# main.net
KiCad netlist of a schematic drawn in Altium Designer
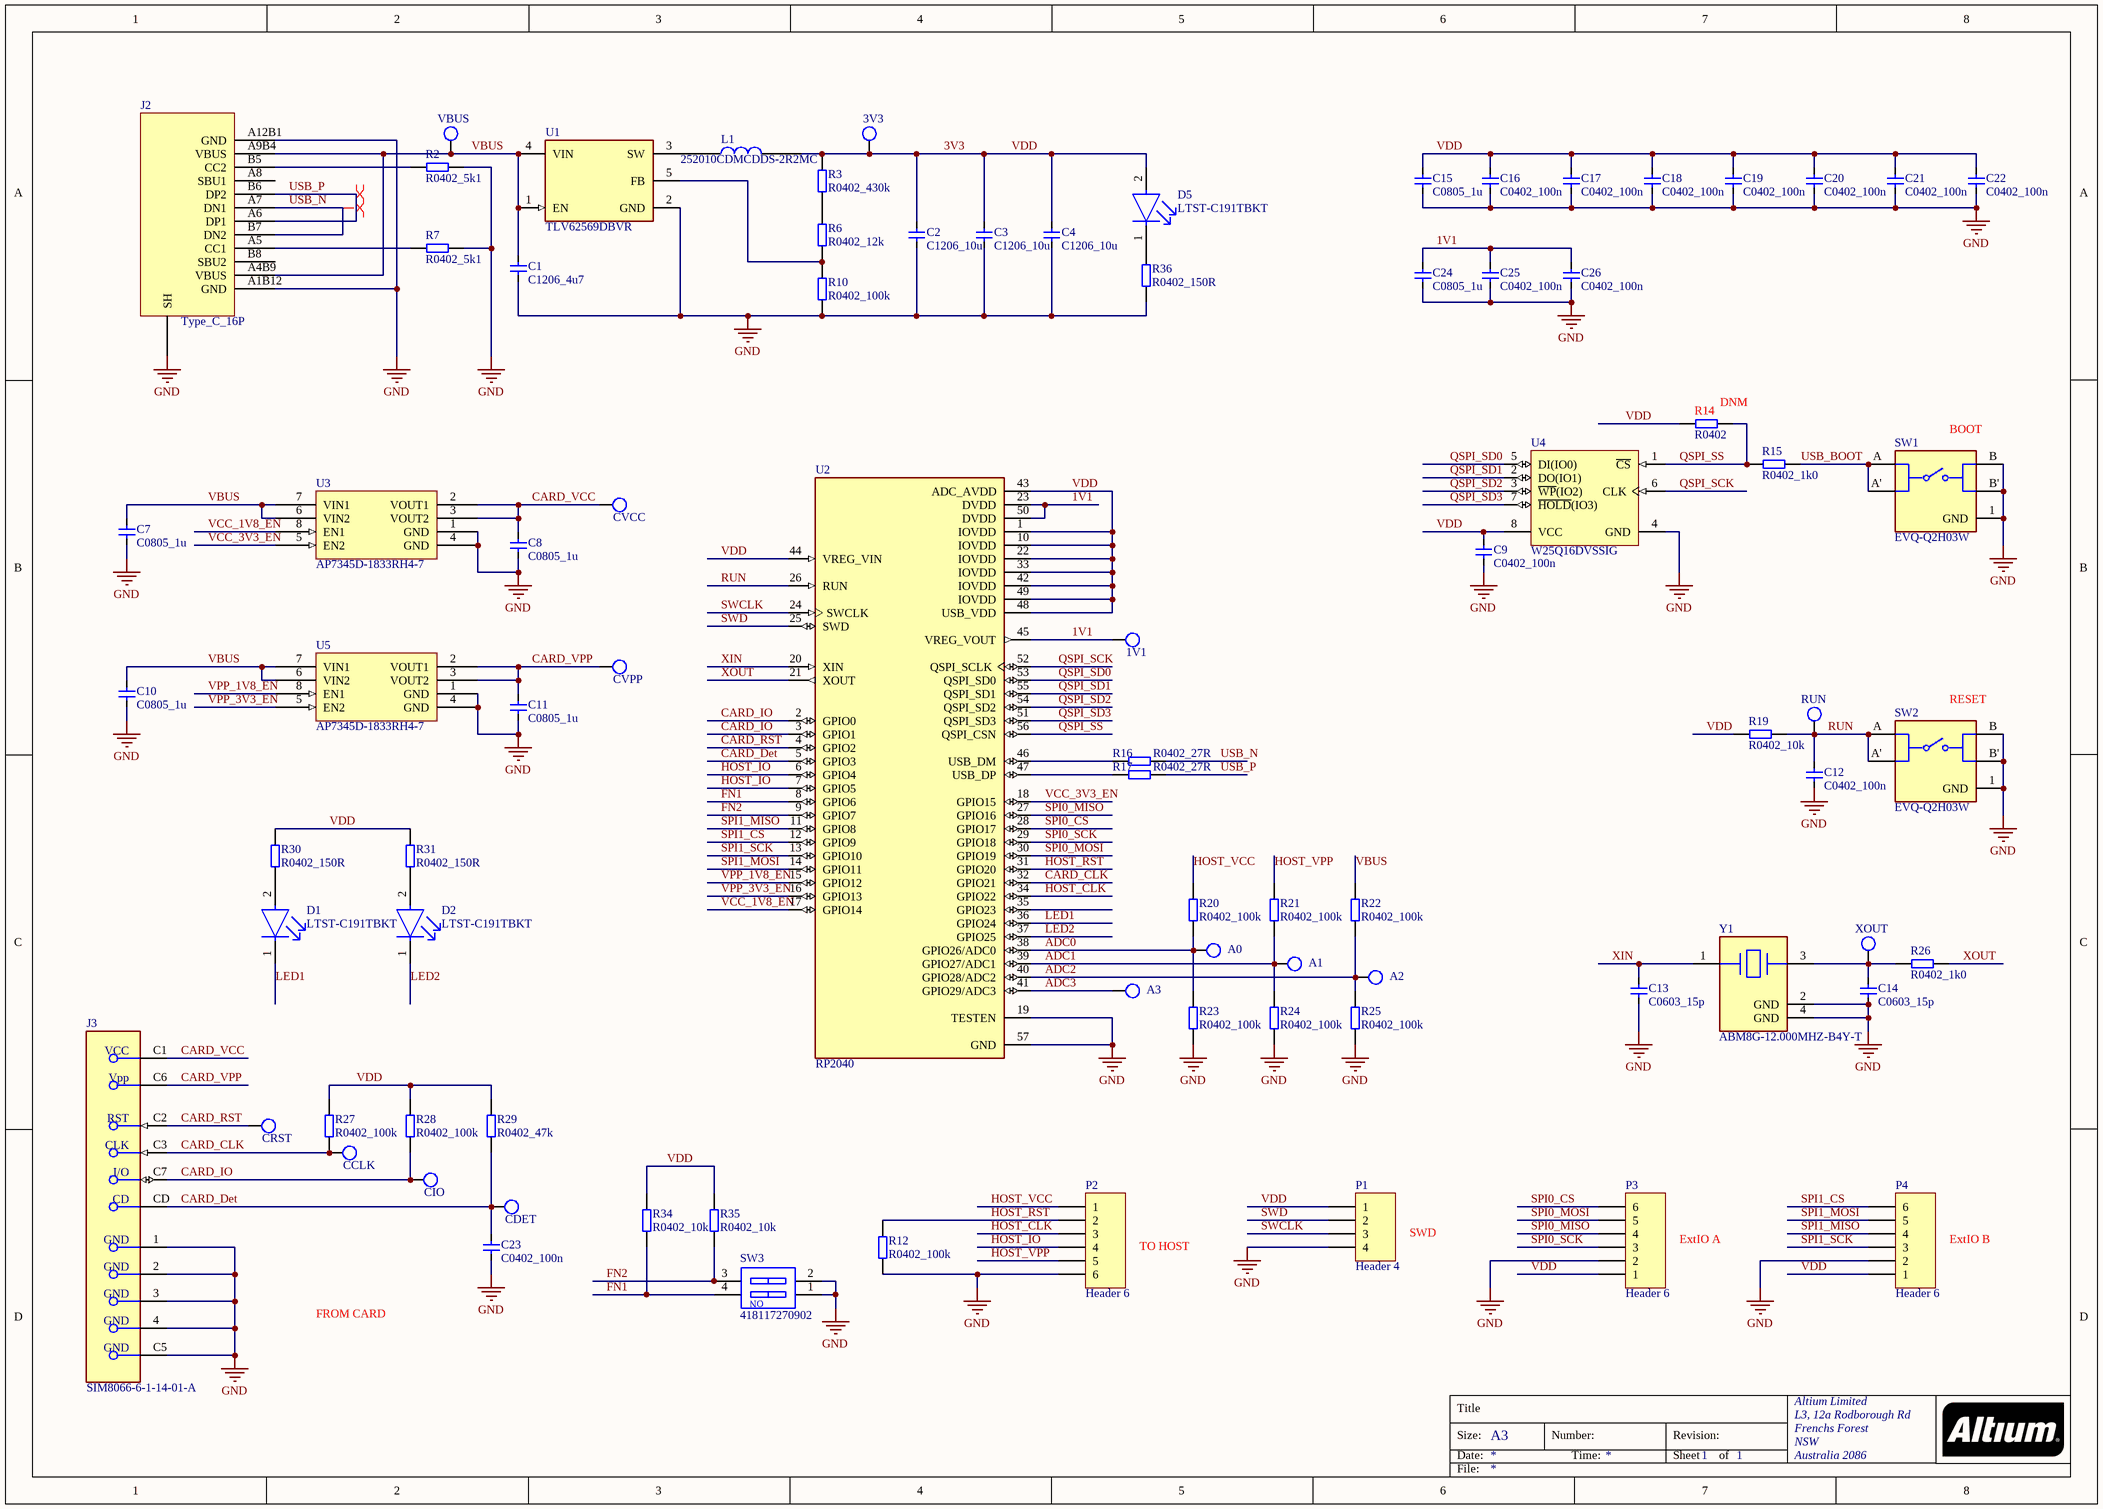
[diagram p0: main.SchDoc]

(export (version "E")
  (design (tool "Eeschema 10.0.6"))
  (components
    (comp (ref "1V1")
      (value "TestPin 1.2R 0.3R")
      (footprint "TestPin_1.2R_0.3R")
      (libsource (lib "LuLib") (part "TestPin 1.2R 0.3R"))
    )
    (comp (ref "3V3")
      (value "TestPin 1.2R 0.3R")
      (footprint "TestPin_1.2R_0.3R")
      (libsource (lib "LuLib") (part "TestPin 1.2R 0.3R"))
    )
    (comp (ref "A0")
      (value "TestPin 1.2R 0.3R")
      (footprint "TestPin_1.2R_0.3R")
      (libsource (lib "LuLib") (part "TestPin 1.2R 0.3R"))
    )
    (comp (ref "A1")
      (value "TestPin 1.2R 0.3R")
      (footprint "TestPin_1.2R_0.3R")
      (libsource (lib "LuLib") (part "TestPin 1.2R 0.3R"))
    )
    (comp (ref "A2")
      (value "TestPin 1.2R 0.3R")
      (footprint "TestPin_1.2R_0.3R")
      (libsource (lib "LuLib") (part "TestPin 1.2R 0.3R"))
    )
    (comp (ref "A3")
      (value "TestPin 1.2R 0.3R")
      (footprint "TestPin_1.2R_0.3R")
      (libsource (lib "LuLib") (part "TestPin 1.2R 0.3R"))
    )
    (comp (ref "C1")
      (value "C1206_4u7")
      (footprint "C1206")
      (fields (field (name "TOLERANCE") "0.1%"))
      (libsource (lib "NyaMoe Internal Altium Server") (part "Cap"))
    )
    (comp (ref "C2")
      (value "C1206_10u")
      (footprint "C1206")
      (fields (field (name "TOLERANCE") "0.1%"))
      (libsource (lib "NyaMoe Internal Altium Server") (part "Cap"))
    )
    (comp (ref "C3")
      (value "C1206_10u")
      (footprint "C1206")
      (fields (field (name "TOLERANCE") "0.1%"))
      (libsource (lib "NyaMoe Internal Altium Server") (part "Cap"))
    )
    (comp (ref "C4")
      (value "C1206_10u")
      (footprint "C1206")
      (fields (field (name "TOLERANCE") "0.1%"))
      (libsource (lib "NyaMoe Internal Altium Server") (part "Cap"))
    )
    (comp (ref "C7")
      (value "C0805_1u")
      (footprint "C0805")
      (fields (field (name "TOLERANCE") "0.1%"))
      (libsource (lib "NyaMoe Internal Altium Server") (part "Cap"))
    )
    (comp (ref "C8")
      (value "C0805_1u")
      (footprint "C0805")
      (fields (field (name "TOLERANCE") "0.1%"))
      (libsource (lib "NyaMoe Internal Altium Server") (part "Cap"))
    )
    (comp (ref "C9")
      (value "C0402_100n")
      (footprint "C0402")
      (fields (field (name "TOLERANCE") "0.1%"))
      (libsource (lib "NyaMoe Internal Altium Server") (part "Cap"))
    )
    (comp (ref "C10")
      (value "C0805_1u")
      (footprint "C0805")
      (fields (field (name "TOLERANCE") "0.1%"))
      (libsource (lib "NyaMoe Internal Altium Server") (part "Cap"))
    )
    (comp (ref "C11")
      (value "C0805_1u")
      (footprint "C0805")
      (fields (field (name "TOLERANCE") "0.1%"))
      (libsource (lib "NyaMoe Internal Altium Server") (part "Cap"))
    )
    (comp (ref "C12")
      (value "C0402_100n")
      (footprint "C0402")
      (fields (field (name "TOLERANCE") "0.1%"))
      (libsource (lib "NyaMoe Internal Altium Server") (part "Cap"))
    )
    (comp (ref "C13")
      (value "C0603_15p")
      (footprint "C0603")
      (fields (field (name "TOLERANCE") "0.05%"))
      (libsource (lib "NyaMoe Internal Altium Server") (part "Cap"))
    )
    (comp (ref "C14")
      (value "C0603_15p")
      (footprint "C0603")
      (fields (field (name "TOLERANCE") "0.05%"))
      (libsource (lib "NyaMoe Internal Altium Server") (part "Cap"))
    )
    (comp (ref "C15")
      (value "C0805_1u")
      (footprint "C0805")
      (fields (field (name "TOLERANCE") "0.1%"))
      (libsource (lib "NyaMoe Internal Altium Server") (part "Cap"))
    )
    (comp (ref "C16")
      (value "C0402_100n")
      (footprint "C0402")
      (fields (field (name "TOLERANCE") "0.1%"))
      (libsource (lib "NyaMoe Internal Altium Server") (part "Cap"))
    )
    (comp (ref "C17")
      (value "C0402_100n")
      (footprint "C0402")
      (fields (field (name "TOLERANCE") "0.1%"))
      (libsource (lib "NyaMoe Internal Altium Server") (part "Cap"))
    )
    (comp (ref "C18")
      (value "C0402_100n")
      (footprint "C0402")
      (fields (field (name "TOLERANCE") "0.1%"))
      (libsource (lib "NyaMoe Internal Altium Server") (part "Cap"))
    )
    (comp (ref "C19")
      (value "C0402_100n")
      (footprint "C0402")
      (fields (field (name "TOLERANCE") "0.1%"))
      (libsource (lib "NyaMoe Internal Altium Server") (part "Cap"))
    )
    (comp (ref "C20")
      (value "C0402_100n")
      (footprint "C0402")
      (fields (field (name "TOLERANCE") "0.1%"))
      (libsource (lib "NyaMoe Internal Altium Server") (part "Cap"))
    )
    (comp (ref "C21")
      (value "C0402_100n")
      (footprint "C0402")
      (fields (field (name "TOLERANCE") "0.1%"))
      (libsource (lib "NyaMoe Internal Altium Server") (part "Cap"))
    )
    (comp (ref "C22")
      (value "C0402_100n")
      (footprint "C0402")
      (fields (field (name "TOLERANCE") "0.1%"))
      (libsource (lib "NyaMoe Internal Altium Server") (part "Cap"))
    )
    (comp (ref "C23")
      (value "C0402_100n")
      (footprint "C0402")
      (fields (field (name "TOLERANCE") "0.1%"))
      (libsource (lib "NyaMoe Internal Altium Server") (part "Cap"))
    )
    (comp (ref "C24")
      (value "C0805_1u")
      (footprint "C0805")
      (fields (field (name "TOLERANCE") "0.1%"))
      (libsource (lib "NyaMoe Internal Altium Server") (part "Cap"))
    )
    (comp (ref "C25")
      (value "C0402_100n")
      (footprint "C0402")
      (fields (field (name "TOLERANCE") "0.1%"))
      (libsource (lib "NyaMoe Internal Altium Server") (part "Cap"))
    )
    (comp (ref "C26")
      (value "C0402_100n")
      (footprint "C0402")
      (fields (field (name "TOLERANCE") "0.1%"))
      (libsource (lib "NyaMoe Internal Altium Server") (part "Cap"))
    )
    (comp (ref "CCLK")
      (value "TestPin 1.2R 0.3R")
      (footprint "TestPin_1.2R_0.3R")
      (libsource (lib "LuLib") (part "TestPin 1.2R 0.3R"))
    )
    (comp (ref "CDET")
      (value "TestPin 1.2R 0.3R")
      (footprint "TestPin_1.2R_0.3R")
      (libsource (lib "LuLib") (part "TestPin 1.2R 0.3R"))
    )
    (comp (ref "CIO")
      (value "TestPin 1.2R 0.3R")
      (footprint "TestPin_1.2R_0.3R")
      (libsource (lib "LuLib") (part "TestPin 1.2R 0.3R"))
    )
    (comp (ref "CRST")
      (value "TestPin 1.2R 0.3R")
      (footprint "TestPin_1.2R_0.3R")
      (libsource (lib "LuLib") (part "TestPin 1.2R 0.3R"))
    )
    (comp (ref "CVCC")
      (value "TestPin 1.2R 0.3R")
      (footprint "TestPin_1.2R_0.3R")
      (libsource (lib "LuLib") (part "TestPin 1.2R 0.3R"))
    )
    (comp (ref "CVPP")
      (value "TestPin 1.2R 0.3R")
      (footprint "TestPin_1.2R_0.3R")
      (libsource (lib "LuLib") (part "TestPin 1.2R 0.3R"))
    )
    (comp (ref "D1")
      (value "LTST-C191TBKT")
      (footprint "FP-LTST-C191TBKT-MFG")
      (description "LED BLUE CLEAR CHIP SMD")
      (libsource (lib "Altium Content Vault") (part "8706943c75ba83719d021d2fdc84c58"))
    )
    (comp (ref "D2")
      (value "LTST-C191TBKT")
      (footprint "FP-LTST-C191TBKT-MFG")
      (description "LED BLUE CLEAR CHIP SMD")
      (libsource (lib "Altium Content Vault") (part "8706943c75ba83719d021d2fdc84c58"))
    )
    (comp (ref "D5")
      (value "LTST-C191TBKT")
      (footprint "FP-LTST-C191TBKT-MFG")
      (description "LED BLUE CLEAR CHIP SMD")
      (libsource (lib "Altium Content Vault") (part "8706943c75ba83719d021d2fdc84c58"))
    )
    (comp (ref "J2")
      (value "Type_C_16P")
      (footprint "Type_C_16P")
      (libsource (lib "LuLib") (part "Type_C_16P"))
    )
    (comp (ref "J3")
      (value "SIM8066-6-1-14-01-A")
      (footprint "FP-SIM8066-6-1-14-01-A-MFG")
      (description "SIM8066-6-1-14-01-A Memory Card Connectors 1.44mm Nano SIM Conn w/Peg and Switch")
      (libsource (lib "Altium Content Vault") (part "1421b091a134f49a34fd3b08e40bfdd"))
    )
    (comp (ref "L1")
      (value "252010CDMCDDS-2R2MC")
      (footprint "INDC2520X10N")
      (description "Fixed Ind 2.2UH 2.5A 97 Mohm SMD")
      (libsource (lib "NyaMoe Internal Altium Server") (part "252010CDMCDDS-2R2MC"))
    )
    (comp (ref "P1")
      (value "Header 4")
      (footprint "HDR1X4")
      (description "Header, 4-Pin")
      (fields (field (name "PUBLISHER") "Altium Limited"))
      (libsource (lib "Miscellaneous Connectors") (part "Header 4"))
    )
    (comp (ref "P2")
      (value "Header 6")
      (footprint "HDR1X6")
      (description "Header, 6-Pin")
      (fields (field (name "PUBLISHER") "Altium Limited"))
      (libsource (lib "Miscellaneous Connectors") (part "Header 6"))
    )
    (comp (ref "P3")
      (value "Header 6")
      (footprint "HDR1X6")
      (description "Header, 6-Pin")
      (fields (field (name "PUBLISHER") "Altium Limited"))
      (libsource (lib "") (part "Header 6_1"))
    )
    (comp (ref "P4")
      (value "Header 6")
      (footprint "HDR1X6")
      (description "Header, 6-Pin")
      (fields (field (name "PUBLISHER") "Altium Limited"))
      (libsource (lib "") (part "Header 6_1"))
    )
    (comp (ref "R2")
      (value "R0402_5k1")
      (footprint "R0402")
      (fields (field (name "TOLERANCE") "1%"))
      (libsource (lib "NyaMoe Internal Altium Server") (part "Res"))
    )
    (comp (ref "R3")
      (value "R0402_430k")
      (footprint "R0402")
      (fields (field (name "TOLERANCE") "1%"))
      (libsource (lib "NyaMoe Internal Altium Server") (part "Res"))
    )
    (comp (ref "R6")
      (value "R0402_12k")
      (footprint "R0402")
      (fields (field (name "TOLERANCE") "1%"))
      (libsource (lib "NyaMoe Internal Altium Server") (part "Res"))
    )
    (comp (ref "R7")
      (value "R0402_5k1")
      (footprint "R0402")
      (fields (field (name "TOLERANCE") "1%"))
      (libsource (lib "NyaMoe Internal Altium Server") (part "Res"))
    )
    (comp (ref "R10")
      (value "R0402_100k")
      (footprint "R0402")
      (fields (field (name "TOLERANCE") "1%"))
      (libsource (lib "NyaMoe Internal Altium Server") (part "Res"))
    )
    (comp (ref "R12")
      (value "R0402_100k")
      (footprint "R0402")
      (fields (field (name "TOLERANCE") "1%"))
      (libsource (lib "NyaMoe Internal Altium Server") (part "Res"))
    )
    (comp (ref "R14")
      (value "R0402")
      (footprint "R0402")
      (fields (field (name "TOLERANCE") "1%"))
      (libsource (lib "NyaMoe Internal Altium Server") (part "Res"))
    )
    (comp (ref "R15")
      (value "R0402_1k0")
      (footprint "R0402")
      (fields (field (name "TOLERANCE") "1%"))
      (libsource (lib "NyaMoe Internal Altium Server") (part "Res"))
    )
    (comp (ref "R16")
      (value "R0402_27R")
      (footprint "R0402")
      (fields (field (name "TOLERANCE") "1%"))
      (libsource (lib "NyaMoe Internal Altium Server") (part "Res"))
    )
    (comp (ref "R17")
      (value "R0402_27R")
      (footprint "R0402")
      (fields (field (name "TOLERANCE") "1%"))
      (libsource (lib "NyaMoe Internal Altium Server") (part "Res"))
    )
    (comp (ref "R19")
      (value "R0402_10k")
      (footprint "R0402")
      (fields (field (name "TOLERANCE") "1%"))
      (libsource (lib "NyaMoe Internal Altium Server") (part "Res"))
    )
    (comp (ref "R20")
      (value "R0402_100k")
      (footprint "R0402")
      (fields (field (name "TOLERANCE") "1%"))
      (libsource (lib "NyaMoe Internal Altium Server") (part "Res"))
    )
    (comp (ref "R21")
      (value "R0402_100k")
      (footprint "R0402")
      (fields (field (name "TOLERANCE") "1%"))
      (libsource (lib "NyaMoe Internal Altium Server") (part "Res"))
    )
    (comp (ref "R22")
      (value "R0402_100k")
      (footprint "R0402")
      (fields (field (name "TOLERANCE") "1%"))
      (libsource (lib "NyaMoe Internal Altium Server") (part "Res"))
    )
    (comp (ref "R23")
      (value "R0402_100k")
      (footprint "R0402")
      (fields (field (name "TOLERANCE") "1%"))
      (libsource (lib "NyaMoe Internal Altium Server") (part "Res"))
    )
    (comp (ref "R24")
      (value "R0402_100k")
      (footprint "R0402")
      (fields (field (name "TOLERANCE") "1%"))
      (libsource (lib "NyaMoe Internal Altium Server") (part "Res"))
    )
    (comp (ref "R25")
      (value "R0402_100k")
      (footprint "R0402")
      (fields (field (name "TOLERANCE") "1%"))
      (libsource (lib "NyaMoe Internal Altium Server") (part "Res"))
    )
    (comp (ref "R26")
      (value "R0402_1k0")
      (footprint "R0402")
      (fields (field (name "TOLERANCE") "1%"))
      (libsource (lib "NyaMoe Internal Altium Server") (part "Res"))
    )
    (comp (ref "R27")
      (value "R0402_100k")
      (footprint "R0402")
      (fields (field (name "TOLERANCE") "1%"))
      (libsource (lib "NyaMoe Internal Altium Server") (part "Res"))
    )
    (comp (ref "R28")
      (value "R0402_100k")
      (footprint "R0402")
      (fields (field (name "TOLERANCE") "1%"))
      (libsource (lib "NyaMoe Internal Altium Server") (part "Res"))
    )
    (comp (ref "R29")
      (value "R0402_47k")
      (footprint "R0402")
      (fields (field (name "TOLERANCE") "1%"))
      (libsource (lib "NyaMoe Internal Altium Server") (part "Res"))
    )
    (comp (ref "R30")
      (value "R0402_150R")
      (footprint "R0402")
      (fields (field (name "TOLERANCE") "1%"))
      (libsource (lib "NyaMoe Internal Altium Server") (part "Res"))
    )
    (comp (ref "R31")
      (value "R0402_150R")
      (footprint "R0402")
      (fields (field (name "TOLERANCE") "1%"))
      (libsource (lib "NyaMoe Internal Altium Server") (part "Res"))
    )
    (comp (ref "R34")
      (value "R0402_10k")
      (footprint "R0402")
      (fields (field (name "TOLERANCE") "1%"))
      (libsource (lib "NyaMoe Internal Altium Server") (part "Res"))
    )
    (comp (ref "R35")
      (value "R0402_10k")
      (footprint "R0402")
      (fields (field (name "TOLERANCE") "1%"))
      (libsource (lib "NyaMoe Internal Altium Server") (part "Res"))
    )
    (comp (ref "R36")
      (value "R0402_150R")
      (footprint "R0402")
      (fields (field (name "TOLERANCE") "1%"))
      (libsource (lib "NyaMoe Internal Altium Server") (part "Res"))
    )
    (comp (ref "RUN")
      (value "TestPin 1.2R 0.3R")
      (footprint "TestPin_1.2R_0.3R")
      (libsource (lib "LuLib") (part "TestPin 1.2R 0.3R"))
    )
    (comp (ref "SW1")
      (value "EVQ-Q2H03W")
      (footprint "FP-EVQ-Q2H03W-MFG")
      (description "SWITCH TACTILE SPST-NO 0.02A 15V")
      (fields
        (field (name "OCTOPART") "https://octopart.com/evq-q2h03w-panasonic-1368538")
        (field (name "MANUFACTURER") "Panasonic Electronic Components")
      )
      (libsource (lib "Altium Content Vault") (part "771f9546cad75bebae6a9b98152ef8d"))
    )
    (comp (ref "SW2")
      (value "EVQ-Q2H03W")
      (footprint "FP-EVQ-Q2H03W-MFG")
      (description "SWITCH TACTILE SPST-NO 0.02A 15V")
      (fields
        (field (name "OCTOPART") "https://octopart.com/evq-q2h03w-panasonic-1368538")
        (field (name "MANUFACTURER") "Panasonic Electronic Components")
      )
      (libsource (lib "Altium Content Vault") (part "771f9546cad75bebae6a9b98152ef8d"))
    )
    (comp (ref "SW3")
      (value "418117270902")
      (footprint "418117270902")
      (libsource (lib "Altium Content Vault") (part "DIP-2"))
    )
    (comp (ref "U1")
      (value "TLV62569DBVR")
      (footprint "FP-DBV0005A-MFG")
      (description "IC REG BUCK ADJ 2A SOT23-5")
      (libsource (lib "Altium Content Vault") (part "f8671745ee5fb9a493b385c735b730b"))
    )
    (comp (ref "U2")
      (value "RP2040")
      (footprint "QFN40P700X700X90-57N")
      (description "RP2040 chip for Raspberry Pi Pico - ARM?Cortex?M0+ MCU 32-Bit")
      (fields (field (name "MF") "Raspberry Pi"))
      (libsource (lib "NyaMoe Internal Altium Server") (part "RP2040"))
    )
    (comp (ref "U3")
      (value "AP7345D-1833RH4-7")
      (footprint "SON127P600-8N")
      (description "Active Positive e4 Fixed Linear Voltage Regulator IC -40C~85C TA 300mA 300mA 5.25V")
      (libsource (lib "NyaMoe Internal Altium Server") (part "AP7345D"))
    )
    (comp (ref "U4")
      (value "W25Q16DVSSIG")
      (footprint "WINB-W25Q16DVSSIG-8_M")
      (description "IC FLASH 16MBIT 104MHZ 8SOIC")
      (fields (field (name "MANUFACTURER") "Winbond"))
      (libsource (lib "Altium Content Vault") (part "WINB-W25Q16DVSSIG-8"))
    )
    (comp (ref "U5")
      (value "AP7345D-1833RH4-7")
      (footprint "SON127P600-8N")
      (description "Active Positive e4 Fixed Linear Voltage Regulator IC -40C~85C TA 300mA 300mA 5.25V")
      (libsource (lib "NyaMoe Internal Altium Server") (part "AP7345D"))
    )
    (comp (ref "VBUS")
      (value "TestPin 1.2R 0.3R")
      (footprint "TestPin_1.2R_0.3R")
      (libsource (lib "LuLib") (part "TestPin 1.2R 0.3R"))
    )
    (comp (ref "XOUT")
      (value "TestPin 1.2R 0.3R")
      (footprint "TestPin_1.2R_0.3R")
      (libsource (lib "LuLib") (part "TestPin 1.2R 0.3R"))
    )
    (comp (ref "Y1")
      (value "ABM8G-12.000MHZ-B4Y-T")
      (footprint "FP-ABM8G-MFG")
      (description "Crystal 12MHz ±30ppm (Tol) ±30ppm (Stability) 10pF FUND 120Ω 4-Pin SMD T/R")
      (fields (field (name "TOLERANCE") "30ppm"))
      (libsource (lib "Altium Content Vault") (part "48e526d86b7f2615d98721063c72f49"))
    )
  )
  (nets
    (net (code "1") (name "/1V1") (class "Default")
      (node (ref "1V1") (pin "0") (pinfunction "0_0") (pintype "passive"))
      (node (ref "C24") (pin "1") (pinfunction "1_1") (pintype "passive"))
      (node (ref "C25") (pin "1") (pinfunction "1_1") (pintype "passive"))
      (node (ref "C26") (pin "1") (pinfunction "1_1") (pintype "passive"))
      (node (ref "U2") (pin "23") (pinfunction "DVDD_23") (pintype "power_in"))
      (node (ref "U2") (pin "45") (pinfunction "VREG_VOUT_45") (pintype "output"))
      (node (ref "U2") (pin "50") (pinfunction "DVDD_50") (pintype "power_in"))
    )
    (net (code "2") (name "/3V3") (class "Default")
      (node (ref "3V3") (pin "0") (pinfunction "0_0") (pintype "passive"))
      (node (ref "C15") (pin "1") (pinfunction "1_1") (pintype "passive"))
      (node (ref "C16") (pin "1") (pinfunction "1_1") (pintype "passive"))
      (node (ref "C17") (pin "1") (pinfunction "1_1") (pintype "passive"))
      (node (ref "C18") (pin "1") (pinfunction "1_1") (pintype "passive"))
      (node (ref "C19") (pin "1") (pinfunction "1_1") (pintype "passive"))
      (node (ref "C2") (pin "1") (pinfunction "1_1") (pintype "passive"))
      (node (ref "C20") (pin "1") (pinfunction "1_1") (pintype "passive"))
      (node (ref "C21") (pin "1") (pinfunction "1_1") (pintype "passive"))
      (node (ref "C22") (pin "1") (pinfunction "1_1") (pintype "passive"))
      (node (ref "C3") (pin "1") (pinfunction "1_1") (pintype "passive"))
      (node (ref "C4") (pin "1") (pinfunction "1_1") (pintype "passive"))
      (node (ref "C9") (pin "1") (pinfunction "1_1") (pintype "passive"))
      (node (ref "D5") (pin "2") (pinfunction "A_2") (pintype "passive"))
      (node (ref "L1") (pin "2") (pinfunction "2_2") (pintype "passive"))
      (node (ref "P1") (pin "1") (pinfunction "1_1") (pintype "passive"))
      (node (ref "P3") (pin "1") (pinfunction "1_1") (pintype "passive"))
      (node (ref "P4") (pin "1") (pinfunction "1_1") (pintype "passive"))
      (node (ref "R14") (pin "1") (pinfunction "1_1") (pintype "passive"))
      (node (ref "R19") (pin "1") (pinfunction "1_1") (pintype "passive"))
      (node (ref "R27") (pin "2") (pinfunction "2_2") (pintype "passive"))
      (node (ref "R28") (pin "2") (pinfunction "2_2") (pintype "passive"))
      (node (ref "R29") (pin "2") (pinfunction "2_2") (pintype "passive"))
      (node (ref "R3") (pin "2") (pinfunction "2_2") (pintype "passive"))
      (node (ref "R30") (pin "2") (pinfunction "2_2") (pintype "passive"))
      (node (ref "R31") (pin "2") (pinfunction "2_2") (pintype "passive"))
      (node (ref "R34") (pin "2") (pinfunction "2_2") (pintype "passive"))
      (node (ref "R35") (pin "2") (pinfunction "2_2") (pintype "passive"))
      (node (ref "U2") (pin "1") (pinfunction "IOVDD_1") (pintype "power_in"))
      (node (ref "U2") (pin "10") (pinfunction "IOVDD_10") (pintype "power_in"))
      (node (ref "U2") (pin "22") (pinfunction "IOVDD_22") (pintype "power_in"))
      (node (ref "U2") (pin "33") (pinfunction "IOVDD_33") (pintype "power_in"))
      (node (ref "U2") (pin "42") (pinfunction "IOVDD_42") (pintype "power_in"))
      (node (ref "U2") (pin "43") (pinfunction "ADC_AVDD_43") (pintype "power_in"))
      (node (ref "U2") (pin "44") (pinfunction "VREG_VIN_44") (pintype "input"))
      (node (ref "U2") (pin "48") (pinfunction "USB_VDD_48") (pintype "power_in"))
      (node (ref "U2") (pin "49") (pinfunction "IOVDD_49") (pintype "power_in"))
      (node (ref "U4") (pin "8") (pinfunction "VCC_8") (pintype "power_in"))
    )
    (net (code "3") (name "/ADC0") (class "Default")
      (node (ref "A0") (pin "0") (pinfunction "0_0") (pintype "passive"))
      (node (ref "R20") (pin "1") (pinfunction "1_1") (pintype "passive"))
      (node (ref "R23") (pin "2") (pinfunction "2_2") (pintype "passive"))
      (node (ref "U2") (pin "38") (pinfunction "GPIO26/ADC0_38") (pintype "bidirectional"))
    )
    (net (code "4") (name "/ADC1") (class "Default")
      (node (ref "A1") (pin "0") (pinfunction "0_0") (pintype "passive"))
      (node (ref "R21") (pin "1") (pinfunction "1_1") (pintype "passive"))
      (node (ref "R24") (pin "2") (pinfunction "2_2") (pintype "passive"))
      (node (ref "U2") (pin "39") (pinfunction "GPIO27/ADC1_39") (pintype "bidirectional"))
    )
    (net (code "5") (name "/ADC2") (class "Default")
      (node (ref "A2") (pin "0") (pinfunction "0_0") (pintype "passive"))
      (node (ref "R22") (pin "1") (pinfunction "1_1") (pintype "passive"))
      (node (ref "R25") (pin "2") (pinfunction "2_2") (pintype "passive"))
      (node (ref "U2") (pin "40") (pinfunction "GPIO28/ADC2_40") (pintype "bidirectional"))
    )
    (net (code "6") (name "/ADC3") (class "Default")
      (node (ref "A3") (pin "0") (pinfunction "0_0") (pintype "passive"))
      (node (ref "U2") (pin "41") (pinfunction "GPIO29/ADC3_41") (pintype "bidirectional"))
    )
    (net (code "7") (name "/CARD_CLK") (class "Default")
      (node (ref "CCLK") (pin "0") (pinfunction "0_0") (pintype "passive"))
      (node (ref "J3") (pin "C3") (pinfunction "CLK_C3") (pintype "input"))
      (node (ref "R27") (pin "1") (pinfunction "1_1") (pintype "passive"))
      (node (ref "U2") (pin "32") (pinfunction "GPIO21_32") (pintype "bidirectional"))
    )
    (net (code "8") (name "/CARD_Det") (class "Default")
      (node (ref "C23") (pin "1") (pinfunction "1_1") (pintype "passive"))
      (node (ref "CDET") (pin "0") (pinfunction "0_0") (pintype "passive"))
      (node (ref "J3") (pin "CD") (pinfunction "CD_CD") (pintype "passive"))
      (node (ref "R29") (pin "1") (pinfunction "1_1") (pintype "passive"))
      (node (ref "U2") (pin "5") (pinfunction "GPIO3_5") (pintype "bidirectional"))
    )
    (net (code "9") (name "/CARD_IO") (class "Default")
      (node (ref "CIO") (pin "0") (pinfunction "0_0") (pintype "passive"))
      (node (ref "J3") (pin "C7") (pinfunction "I/O_C7") (pintype "bidirectional"))
      (node (ref "R28") (pin "1") (pinfunction "1_1") (pintype "passive"))
      (node (ref "U2") (pin "2") (pinfunction "GPIO0_2") (pintype "bidirectional"))
      (node (ref "U2") (pin "3") (pinfunction "GPIO1_3") (pintype "bidirectional"))
    )
    (net (code "10") (name "/CARD_RST") (class "Default")
      (node (ref "CRST") (pin "0") (pinfunction "0_0") (pintype "passive"))
      (node (ref "J3") (pin "C2") (pinfunction "RST_C2") (pintype "input"))
      (node (ref "U2") (pin "4") (pinfunction "GPIO2_4") (pintype "bidirectional"))
    )
    (net (code "11") (name "/CARD_VCC") (class "Default")
      (node (ref "C8") (pin "1") (pinfunction "1_1") (pintype "passive"))
      (node (ref "CVCC") (pin "0") (pinfunction "0_0") (pintype "passive"))
      (node (ref "J3") (pin "C1") (pinfunction "VCC_C1") (pintype "power_in"))
      (node (ref "U3") (pin "2") (pinfunction "VOUT1_2") (pintype "power_in"))
      (node (ref "U3") (pin "3") (pinfunction "VOUT2_3") (pintype "power_in"))
    )
    (net (code "12") (name "/CARD_VPP") (class "Default")
      (node (ref "C11") (pin "1") (pinfunction "1_1") (pintype "passive"))
      (node (ref "CVPP") (pin "0") (pinfunction "0_0") (pintype "passive"))
      (node (ref "J3") (pin "C6") (pinfunction "Vpp_C6") (pintype "power_in"))
      (node (ref "U5") (pin "2") (pinfunction "VOUT1_2") (pintype "power_in"))
      (node (ref "U5") (pin "3") (pinfunction "VOUT2_3") (pintype "power_in"))
    )
    (net (code "13") (name "/FN1") (class "Default")
      (node (ref "R34") (pin "1") (pinfunction "1_1") (pintype "passive"))
      (node (ref "SW3") (pin "4") (pinfunction "4_4") (pintype "passive"))
      (node (ref "U2") (pin "8") (pinfunction "GPIO6_8") (pintype "bidirectional"))
    )
    (net (code "14") (name "/FN2") (class "Default")
      (node (ref "R35") (pin "1") (pinfunction "1_1") (pintype "passive"))
      (node (ref "SW3") (pin "3") (pinfunction "3_3") (pintype "passive"))
      (node (ref "U2") (pin "9") (pinfunction "GPIO7_9") (pintype "bidirectional"))
    )
    (net (code "15") (name "/HOST_CLK") (class "Default")
      (node (ref "P2") (pin "3") (pinfunction "3_3") (pintype "passive"))
      (node (ref "U2") (pin "34") (pinfunction "GPIO22_34") (pintype "bidirectional"))
    )
    (net (code "16") (name "/HOST_IO") (class "Default")
      (node (ref "P2") (pin "4") (pinfunction "4_4") (pintype "passive"))
      (node (ref "U2") (pin "6") (pinfunction "GPIO4_6") (pintype "bidirectional"))
      (node (ref "U2") (pin "7") (pinfunction "GPIO5_7") (pintype "bidirectional"))
    )
    (net (code "17") (name "/HOST_RST") (class "Default")
      (node (ref "P2") (pin "2") (pinfunction "2_2") (pintype "passive"))
      (node (ref "R12") (pin "2") (pinfunction "2_2") (pintype "passive"))
      (node (ref "U2") (pin "31") (pinfunction "GPIO20_31") (pintype "bidirectional"))
    )
    (net (code "18") (name "/HOST_VCC") (class "Default")
      (node (ref "P2") (pin "1") (pinfunction "1_1") (pintype "passive"))
      (node (ref "R20") (pin "2") (pinfunction "2_2") (pintype "passive"))
    )
    (net (code "19") (name "/HOST_VPP") (class "Default")
      (node (ref "P2") (pin "5") (pinfunction "5_5") (pintype "passive"))
      (node (ref "R21") (pin "2") (pinfunction "2_2") (pintype "passive"))
    )
    (net (code "20") (name "/LED1") (class "Default")
      (node (ref "D1") (pin "1") (pinfunction "C_1") (pintype "passive"))
      (node (ref "U2") (pin "36") (pinfunction "GPIO24_36") (pintype "bidirectional"))
    )
    (net (code "21") (name "/LED2") (class "Default")
      (node (ref "D2") (pin "1") (pinfunction "C_1") (pintype "passive"))
      (node (ref "U2") (pin "37") (pinfunction "GPIO25_37") (pintype "bidirectional"))
    )
    (net (code "22") (name "/QSPI_SCK") (class "Default")
      (node (ref "U2") (pin "52") (pinfunction "QSPI_SCLK_52") (pintype "bidirectional"))
      (node (ref "U4") (pin "6") (pinfunction "CLK_6") (pintype "input"))
    )
    (net (code "23") (name "/QSPI_SD0") (class "Default")
      (node (ref "U2") (pin "53") (pinfunction "QSPI_SD0_53") (pintype "bidirectional"))
      (node (ref "U4") (pin "5") (pinfunction "DI(IO0)_5") (pintype "bidirectional"))
    )
    (net (code "24") (name "/QSPI_SD1") (class "Default")
      (node (ref "U2") (pin "55") (pinfunction "QSPI_SD1_55") (pintype "bidirectional"))
      (node (ref "U4") (pin "2") (pinfunction "DO(IO1)_2") (pintype "bidirectional"))
    )
    (net (code "25") (name "/QSPI_SD2") (class "Default")
      (node (ref "U2") (pin "54") (pinfunction "QSPI_SD2_54") (pintype "bidirectional"))
      (node (ref "U4") (pin "3") (pinfunction "~{WP}(IO2)_3") (pintype "bidirectional"))
    )
    (net (code "26") (name "/QSPI_SD3") (class "Default")
      (node (ref "U2") (pin "51") (pinfunction "QSPI_SD3_51") (pintype "bidirectional"))
      (node (ref "U4") (pin "7") (pinfunction "~{HOLD}(IO3)_7") (pintype "bidirectional"))
    )
    (net (code "27") (name "/QSPI_SS") (class "Default")
      (node (ref "R14") (pin "2") (pinfunction "2_2") (pintype "passive"))
      (node (ref "R15") (pin "1") (pinfunction "1_1") (pintype "passive"))
      (node (ref "U2") (pin "56") (pinfunction "QSPI_CSN_56") (pintype "bidirectional"))
      (node (ref "U4") (pin "1") (pinfunction "~{CS}_1") (pintype "input"))
    )
    (net (code "28") (name "/RUN") (class "Default")
      (node (ref "C12") (pin "1") (pinfunction "1_1") (pintype "passive"))
      (node (ref "R19") (pin "2") (pinfunction "2_2") (pintype "passive"))
      (node (ref "RUN") (pin "0") (pinfunction "0_0") (pintype "passive"))
      (node (ref "SW2") (pin "A") (pinfunction "A_A") (pintype "passive"))
      (node (ref "SW2") (pin "A'") (pinfunction "A'_A'") (pintype "passive"))
      (node (ref "U2") (pin "26") (pinfunction "RUN_26") (pintype "input"))
    )
    (net (code "29") (name "/SPI0_CS") (class "Default")
      (node (ref "P3") (pin "6") (pinfunction "6_6") (pintype "passive"))
      (node (ref "U2") (pin "28") (pinfunction "GPIO17_28") (pintype "bidirectional"))
    )
    (net (code "30") (name "/SPI0_MISO") (class "Default")
      (node (ref "P3") (pin "4") (pinfunction "4_4") (pintype "passive"))
      (node (ref "U2") (pin "27") (pinfunction "GPIO16_27") (pintype "bidirectional"))
    )
    (net (code "31") (name "/SPI0_MOSI") (class "Default")
      (node (ref "P3") (pin "5") (pinfunction "5_5") (pintype "passive"))
      (node (ref "U2") (pin "30") (pinfunction "GPIO19_30") (pintype "bidirectional"))
    )
    (net (code "32") (name "/SPI0_SCK") (class "Default")
      (node (ref "P3") (pin "3") (pinfunction "3_3") (pintype "passive"))
      (node (ref "U2") (pin "29") (pinfunction "GPIO18_29") (pintype "bidirectional"))
    )
    (net (code "33") (name "/SPI1_CS") (class "Default")
      (node (ref "P4") (pin "6") (pinfunction "6_6") (pintype "passive"))
      (node (ref "U2") (pin "12") (pinfunction "GPIO9_12") (pintype "bidirectional"))
    )
    (net (code "34") (name "/SPI1_MISO") (class "Default")
      (node (ref "P4") (pin "4") (pinfunction "4_4") (pintype "passive"))
      (node (ref "U2") (pin "11") (pinfunction "GPIO8_11") (pintype "bidirectional"))
    )
    (net (code "35") (name "/SPI1_MOSI") (class "Default")
      (node (ref "P4") (pin "5") (pinfunction "5_5") (pintype "passive"))
      (node (ref "U2") (pin "14") (pinfunction "GPIO11_14") (pintype "bidirectional"))
    )
    (net (code "36") (name "/SPI1_SCK") (class "Default")
      (node (ref "P4") (pin "3") (pinfunction "3_3") (pintype "passive"))
      (node (ref "U2") (pin "13") (pinfunction "GPIO10_13") (pintype "bidirectional"))
    )
    (net (code "37") (name "/SWCLK") (class "Default")
      (node (ref "P1") (pin "3") (pinfunction "3_3") (pintype "passive"))
      (node (ref "U2") (pin "24") (pinfunction "SWCLK_24") (pintype "input"))
    )
    (net (code "38") (name "/SWD") (class "Default")
      (node (ref "P1") (pin "2") (pinfunction "2_2") (pintype "passive"))
      (node (ref "U2") (pin "25") (pinfunction "SWD_25") (pintype "bidirectional"))
    )
    (net (code "39") (name "/USB_BOOT") (class "Default")
      (node (ref "R15") (pin "2") (pinfunction "2_2") (pintype "passive"))
      (node (ref "SW1") (pin "A") (pinfunction "A_A") (pintype "passive"))
      (node (ref "SW1") (pin "A'") (pinfunction "A'_A'") (pintype "passive"))
    )
    (net (code "40") (name "/USB_N") (class "Default")
      (node (ref "J2") (pin "A7") (pinfunction "DN1_A7") (pintype "passive"))
      (node (ref "J2") (pin "B7") (pinfunction "DN2_B7") (pintype "passive"))
      (node (ref "R16") (pin "2") (pinfunction "2_2") (pintype "passive"))
    )
    (net (code "41") (name "/USB_P") (class "Default")
      (node (ref "J2") (pin "A6") (pinfunction "DP1_A6") (pintype "passive"))
      (node (ref "J2") (pin "B6") (pinfunction "DP2_B6") (pintype "passive"))
      (node (ref "R17") (pin "2") (pinfunction "2_2") (pintype "passive"))
    )
    (net (code "42") (name "/VBUS") (class "Default")
      (node (ref "C1") (pin "1") (pinfunction "1_1") (pintype "passive"))
      (node (ref "C10") (pin "1") (pinfunction "1_1") (pintype "passive"))
      (node (ref "C7") (pin "1") (pinfunction "1_1") (pintype "passive"))
      (node (ref "J2") (pin "A4B9") (pinfunction "VBUS_A4B9") (pintype "passive"))
      (node (ref "J2") (pin "A9B4") (pinfunction "VBUS_A9B4") (pintype "passive"))
      (node (ref "R22") (pin "2") (pinfunction "2_2") (pintype "passive"))
      (node (ref "U1") (pin "1") (pinfunction "EN_1") (pintype "input"))
      (node (ref "U1") (pin "4") (pinfunction "VIN_4") (pintype "power_in"))
      (node (ref "U3") (pin "6") (pinfunction "VIN2_6") (pintype "power_in"))
      (node (ref "U3") (pin "7") (pinfunction "VIN1_7") (pintype "power_in"))
      (node (ref "U5") (pin "6") (pinfunction "VIN2_6") (pintype "power_in"))
      (node (ref "U5") (pin "7") (pinfunction "VIN1_7") (pintype "power_in"))
      (node (ref "VBUS") (pin "0") (pinfunction "0_0") (pintype "passive"))
    )
    (net (code "43") (name "/VCC_1V8_EN") (class "Default")
      (node (ref "U2") (pin "17") (pinfunction "GPIO14_17") (pintype "bidirectional"))
      (node (ref "U3") (pin "8") (pinfunction "EN1_8") (pintype "input"))
    )
    (net (code "44") (name "/VCC_3V3_EN") (class "Default")
      (node (ref "U2") (pin "18") (pinfunction "GPIO15_18") (pintype "bidirectional"))
      (node (ref "U3") (pin "5") (pinfunction "EN2_5") (pintype "input"))
    )
    (net (code "45") (name "/VPP_1V8_EN") (class "Default")
      (node (ref "U2") (pin "15") (pinfunction "GPIO12_15") (pintype "bidirectional"))
      (node (ref "U5") (pin "8") (pinfunction "EN1_8") (pintype "input"))
    )
    (net (code "46") (name "/VPP_3V3_EN") (class "Default")
      (node (ref "U2") (pin "16") (pinfunction "GPIO13_16") (pintype "bidirectional"))
      (node (ref "U5") (pin "5") (pinfunction "EN2_5") (pintype "input"))
    )
    (net (code "47") (name "/XIN") (class "Default")
      (node (ref "C13") (pin "1") (pinfunction "1_1") (pintype "passive"))
      (node (ref "U2") (pin "20") (pinfunction "XIN_20") (pintype "input"))
      (node (ref "Y1") (pin "1") (pinfunction "1_1") (pintype "passive"))
    )
    (net (code "48") (name "/XOUT") (class "Default")
      (node (ref "R26") (pin "2") (pinfunction "2_2") (pintype "passive"))
      (node (ref "U2") (pin "21") (pinfunction "XOUT_21") (pintype "output"))
    )
    (net (code "49") (name "GND") (class "Default")
      (node (ref "C1") (pin "2") (pinfunction "2_2") (pintype "passive"))
      (node (ref "C10") (pin "2") (pinfunction "2_2") (pintype "passive"))
      (node (ref "C11") (pin "2") (pinfunction "2_2") (pintype "passive"))
      (node (ref "C12") (pin "2") (pinfunction "2_2") (pintype "passive"))
      (node (ref "C13") (pin "2") (pinfunction "2_2") (pintype "passive"))
      (node (ref "C14") (pin "2") (pinfunction "2_2") (pintype "passive"))
      (node (ref "C15") (pin "2") (pinfunction "2_2") (pintype "passive"))
      (node (ref "C16") (pin "2") (pinfunction "2_2") (pintype "passive"))
      (node (ref "C17") (pin "2") (pinfunction "2_2") (pintype "passive"))
      (node (ref "C18") (pin "2") (pinfunction "2_2") (pintype "passive"))
      (node (ref "C19") (pin "2") (pinfunction "2_2") (pintype "passive"))
      (node (ref "C2") (pin "2") (pinfunction "2_2") (pintype "passive"))
      (node (ref "C20") (pin "2") (pinfunction "2_2") (pintype "passive"))
      (node (ref "C21") (pin "2") (pinfunction "2_2") (pintype "passive"))
      (node (ref "C22") (pin "2") (pinfunction "2_2") (pintype "passive"))
      (node (ref "C23") (pin "2") (pinfunction "2_2") (pintype "passive"))
      (node (ref "C24") (pin "2") (pinfunction "2_2") (pintype "passive"))
      (node (ref "C25") (pin "2") (pinfunction "2_2") (pintype "passive"))
      (node (ref "C26") (pin "2") (pinfunction "2_2") (pintype "passive"))
      (node (ref "C3") (pin "2") (pinfunction "2_2") (pintype "passive"))
      (node (ref "C4") (pin "2") (pinfunction "2_2") (pintype "passive"))
      (node (ref "C7") (pin "2") (pinfunction "2_2") (pintype "passive"))
      (node (ref "C8") (pin "2") (pinfunction "2_2") (pintype "passive"))
      (node (ref "C9") (pin "2") (pinfunction "2_2") (pintype "passive"))
      (node (ref "J2") (pin "0") (pinfunction "SH_0") (pintype "passive"))
      (node (ref "J2") (pin "A12B1") (pinfunction "GND_A12B1") (pintype "passive"))
      (node (ref "J2") (pin "A1B12") (pinfunction "GND_A1B12") (pintype "passive"))
      (node (ref "J3") (pin "1") (pinfunction "GND_1") (pintype "power_in"))
      (node (ref "J3") (pin "2") (pinfunction "GND_2") (pintype "power_in"))
      (node (ref "J3") (pin "3") (pinfunction "GND_3") (pintype "power_in"))
      (node (ref "J3") (pin "4") (pinfunction "GND_4") (pintype "power_in"))
      (node (ref "J3") (pin "C5") (pinfunction "GND_C5") (pintype "power_in"))
      (node (ref "P1") (pin "4") (pinfunction "4_4") (pintype "passive"))
      (node (ref "P2") (pin "6") (pinfunction "6_6") (pintype "passive"))
      (node (ref "P3") (pin "2") (pinfunction "2_2") (pintype "passive"))
      (node (ref "P4") (pin "2") (pinfunction "2_2") (pintype "passive"))
      (node (ref "R10") (pin "1") (pinfunction "1_1") (pintype "passive"))
      (node (ref "R12") (pin "1") (pinfunction "1_1") (pintype "passive"))
      (node (ref "R2") (pin "2") (pinfunction "2_2") (pintype "passive"))
      (node (ref "R23") (pin "1") (pinfunction "1_1") (pintype "passive"))
      (node (ref "R24") (pin "1") (pinfunction "1_1") (pintype "passive"))
      (node (ref "R25") (pin "1") (pinfunction "1_1") (pintype "passive"))
      (node (ref "R36") (pin "1") (pinfunction "1_1") (pintype "passive"))
      (node (ref "R7") (pin "2") (pinfunction "2_2") (pintype "passive"))
      (node (ref "SW1") (pin "1") (pinfunction "GND_1") (pintype "power_in"))
      (node (ref "SW1") (pin "B") (pinfunction "B_B") (pintype "passive"))
      (node (ref "SW1") (pin "B'") (pinfunction "B'_B'") (pintype "passive"))
      (node (ref "SW2") (pin "1") (pinfunction "GND_1") (pintype "power_in"))
      (node (ref "SW2") (pin "B") (pinfunction "B_B") (pintype "passive"))
      (node (ref "SW2") (pin "B'") (pinfunction "B'_B'") (pintype "passive"))
      (node (ref "SW3") (pin "1") (pinfunction "1_1") (pintype "passive"))
      (node (ref "SW3") (pin "2") (pinfunction "2_2") (pintype "passive"))
      (node (ref "U1") (pin "2") (pinfunction "GND_2") (pintype "power_in"))
      (node (ref "U2") (pin "19") (pinfunction "TESTEN_19") (pintype "passive"))
      (node (ref "U2") (pin "57") (pinfunction "GND_57") (pintype "power_in"))
      (node (ref "U3") (pin "1") (pinfunction "GND_1") (pintype "power_in"))
      (node (ref "U3") (pin "4") (pinfunction "GND_4") (pintype "power_in"))
      (node (ref "U4") (pin "4") (pinfunction "GND_4") (pintype "power_in"))
      (node (ref "U5") (pin "1") (pinfunction "GND_1") (pintype "power_in"))
      (node (ref "U5") (pin "4") (pinfunction "GND_4") (pintype "power_in"))
      (node (ref "Y1") (pin "2") (pinfunction "GND_2") (pintype "power_in"))
      (node (ref "Y1") (pin "4") (pinfunction "GND_4") (pintype "power_in"))
    )
    (net (code "50") (name "Net-(C14-Pad1)") (class "Default")
      (node (ref "C14") (pin "1") (pinfunction "1_1") (pintype "passive"))
      (node (ref "R26") (pin "1") (pinfunction "1_1") (pintype "passive"))
      (node (ref "XOUT") (pin "0") (pinfunction "0_0") (pintype "passive"))
      (node (ref "Y1") (pin "3") (pinfunction "3_3") (pintype "passive"))
    )
    (net (code "51") (name "Net-(D1-A)") (class "Default")
      (node (ref "D1") (pin "2") (pinfunction "A_2") (pintype "passive"))
      (node (ref "R30") (pin "1") (pinfunction "1_1") (pintype "passive"))
    )
    (net (code "52") (name "Net-(D2-A)") (class "Default")
      (node (ref "D2") (pin "2") (pinfunction "A_2") (pintype "passive"))
      (node (ref "R31") (pin "1") (pinfunction "1_1") (pintype "passive"))
    )
    (net (code "53") (name "Net-(D5-C)") (class "Default")
      (node (ref "D5") (pin "1") (pinfunction "C_1") (pintype "passive"))
      (node (ref "R36") (pin "2") (pinfunction "2_2") (pintype "passive"))
    )
    (net (code "54") (name "Net-(J2-CC1)") (class "Default")
      (node (ref "J2") (pin "A5") (pinfunction "CC1_A5") (pintype "passive"))
      (node (ref "R7") (pin "1") (pinfunction "1_1") (pintype "passive"))
    )
    (net (code "55") (name "Net-(J2-CC2)") (class "Default")
      (node (ref "J2") (pin "B5") (pinfunction "CC2_B5") (pintype "passive"))
      (node (ref "R2") (pin "1") (pinfunction "1_1") (pintype "passive"))
    )
    (net (code "56") (name "Net-(R3-Pad1)") (class "Default")
      (node (ref "R3") (pin "1") (pinfunction "1_1") (pintype "passive"))
      (node (ref "R6") (pin "2") (pinfunction "2_2") (pintype "passive"))
    )
    (net (code "57") (name "Net-(U1-FB)") (class "Default")
      (node (ref "R10") (pin "2") (pinfunction "2_2") (pintype "passive"))
      (node (ref "R6") (pin "1") (pinfunction "1_1") (pintype "passive"))
      (node (ref "U1") (pin "5") (pinfunction "FB_5") (pintype "passive"))
    )
    (net (code "58") (name "Net-(U1-SW)") (class "Default")
      (node (ref "L1") (pin "1") (pinfunction "1_1") (pintype "passive"))
      (node (ref "U1") (pin "3") (pinfunction "SW_3") (pintype "power_in"))
    )
    (net (code "59") (name "Net-(U2-USB_DM)") (class "Default")
      (node (ref "R16") (pin "1") (pinfunction "1_1") (pintype "passive"))
      (node (ref "U2") (pin "46") (pinfunction "USB_DM_46") (pintype "bidirectional"))
    )
    (net (code "60") (name "Net-(U2-USB_DP)") (class "Default")
      (node (ref "R17") (pin "1") (pinfunction "1_1") (pintype "passive"))
      (node (ref "U2") (pin "47") (pinfunction "USB_DP_47") (pintype "bidirectional"))
    )
    (net (code "61") (name "unconnected-(J2-SBU1-PadA8)") (class "Default")
      (node (ref "J2") (pin "A8") (pinfunction "SBU1_A8") (pintype "passive"))
    )
    (net (code "62") (name "unconnected-(J2-SBU2-PadB8)") (class "Default")
      (node (ref "J2") (pin "B8") (pinfunction "SBU2_B8") (pintype "passive"))
    )
    (net (code "63") (name "unconnected-(U2-GPIO23-Pad35)") (class "Default")
      (node (ref "U2") (pin "35") (pinfunction "GPIO23_35") (pintype "bidirectional"))
    )
  )
)
